# USB-C.net
KiCad netlist of a schematic drawn in Altium Designer
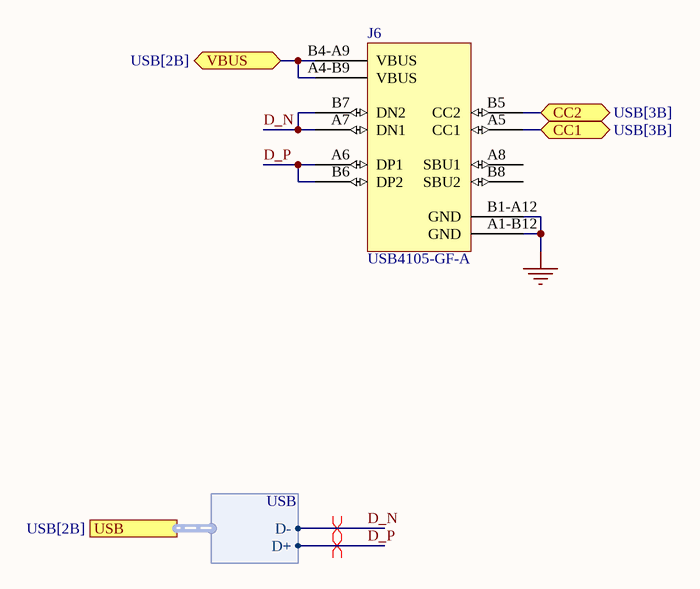
[diagram p0: USB-C.SchDoc]

(export (version "E")
  (design (tool "Eeschema 10.0.6"))
  (components
    (comp (ref "J6")
      (value "USB4105-GF-A")
      (footprint "USB4105_GCT")
      (description "No Description Available")
      (fields (field (name "COPYRIGHT") "Copyright (C) 2023 Ultra Librarian. All rights reserved."))
      (libsource (lib "Twill Technology Inc") (part "USB4105-GF-A"))
    )
  )
  (nets
    (net (code "2") (name "/CC1") (class "Default")
      (node (ref "J6") (pin "A5") (pinfunction "CC1_A5") (pintype "bidirectional"))
    )
    (net (code "3") (name "/CC2") (class "Default")
      (node (ref "J6") (pin "B5") (pinfunction "CC2_B5") (pintype "bidirectional"))
    )
    (net (code "4") (name "/D_N") (class "Default")
      (node (ref "J6") (pin "A7") (pinfunction "DN1_A7") (pintype "bidirectional"))
      (node (ref "J6") (pin "B7") (pinfunction "DN2_B7") (pintype "bidirectional"))
    )
    (net (code "5") (name "/D_P") (class "Default")
      (node (ref "J6") (pin "A6") (pinfunction "DP1_A6") (pintype "bidirectional"))
      (node (ref "J6") (pin "B6") (pinfunction "DP2_B6") (pintype "bidirectional"))
    )
    (net (code "6") (name "/VBUS") (class "Default")
      (node (ref "J6") (pin "A4-B9") (pinfunction "VBUS_A4-B9") (pintype "power_in"))
      (node (ref "J6") (pin "B4-A9") (pinfunction "VBUS_B4-A9") (pintype "power_in"))
    )
    (net (code "8") (name "GND") (class "Default")
      (node (ref "J6") (pin "A1-B12") (pinfunction "GND_A1-B12") (pintype "passive"))
      (node (ref "J6") (pin "B1-A12") (pinfunction "GND_B1-A12") (pintype "passive"))
    )
    (net (code "9") (name "unconnected-(J6-SBU1-PadA8)") (class "Default")
      (node (ref "J6") (pin "A8") (pinfunction "SBU1_A8") (pintype "bidirectional"))
    )
    (net (code "10") (name "unconnected-(J6-SBU2-PadB8)") (class "Default")
      (node (ref "J6") (pin "B8") (pinfunction "SBU2_B8") (pintype "bidirectional"))
    )
  )
)
